# Sensor.net
KiCad netlist of a schematic drawn in Altium Designer
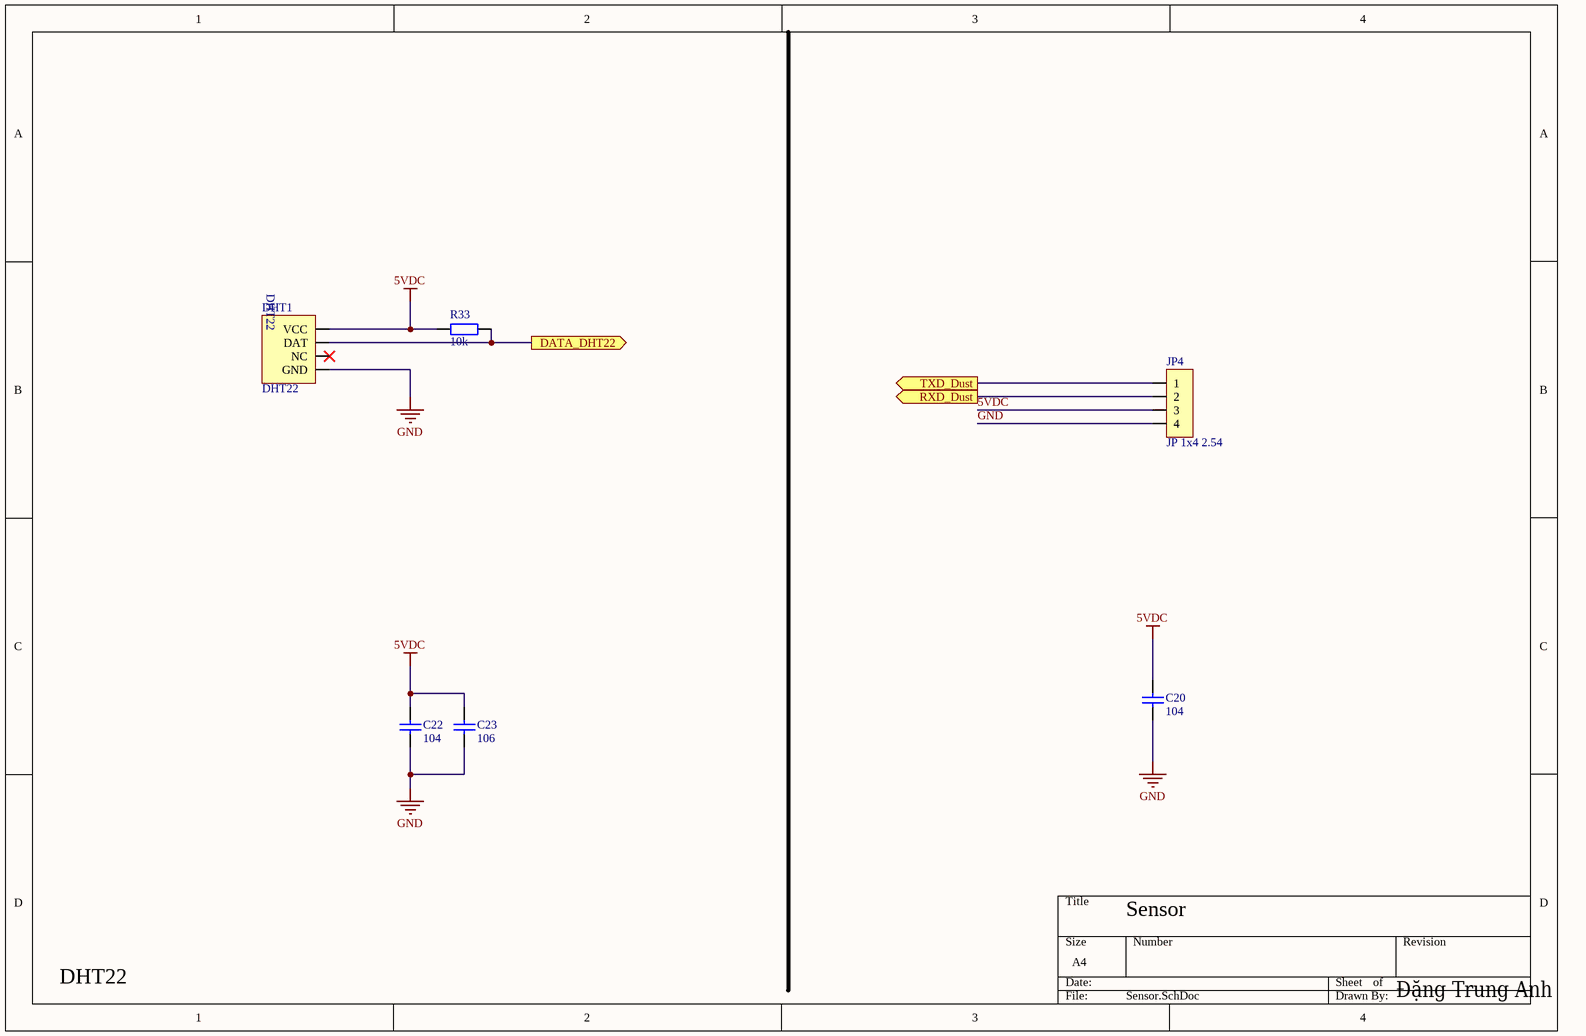
[diagram p0: Sensor.SchDoc]

(export (version "E")
  (design (tool "Eeschema 10.0.6"))
  (components
    (comp (ref "C20")
      (value "104")
      (footprint "tu 0603")
      (description "Dán")
      (libsource (lib "Altium_Lib_by_KhueNguyenCreator") (part "Tu 0603 104 50V 10%"))
    )
    (comp (ref "C22")
      (value "104")
      (footprint "tu 0603")
      (description "Dán")
      (libsource (lib "Altium_Lib_by_KhueNguyenCreator") (part "Tu 0603 104 50V 10%"))
    )
    (comp (ref "C23")
      (value "106")
      (footprint "tu 0603")
      (description "Dán")
      (libsource (lib "THU VIEN SCH") (part "Tu 0603 106 16V 20%"))
    )
    (comp (ref "DHT1")
      (value "DHT22")
      (footprint "DHT22")
      (fields
        (field (name "MANUFACTURER") "Würth Elektronik eiSos GmbH")
        (field (name "PARTNO") "613004143121")
        (field (name "CREATED BY") "Karrer Zheng")
      )
      (libsource (lib "TechMT.VN_Lib_Project v2") (part "DHT22"))
    )
    (comp (ref "JP4")
      (value "JP 1x4 2.54")
      (footprint "JP 1x4 DC")
      (description "Cắm")
      (libsource (lib "Altium_Lib_by_KhueNguyenCreator") (part "JP 1x4 2.54 Duc Cong"))
    )
    (comp (ref "R33")
      (value "10k")
      (footprint "tro smd 0603")
      (description "Dán")
      (libsource (lib "THU VIEN SCH") (part "Tro 0603 1% 10k"))
    )
  )
  (nets
    (net (code "1") (name "/DATA_DHT22") (class "Default")
      (node (ref "DHT1") (pin "2") (pinfunction "DAT_2") (pintype "passive"))
      (node (ref "R33") (pin "1") (pinfunction "1_1") (pintype "passive"))
    )
    (net (code "2") (name "/RXD_Dust") (class "Default")
      (node (ref "JP4") (pin "2") (pinfunction "2_2") (pintype "passive"))
    )
    (net (code "3") (name "/TXD_Dust") (class "Default")
      (node (ref "JP4") (pin "1") (pinfunction "1_1") (pintype "passive"))
    )
    (net (code "4") (name "5VDC") (class "Default")
      (node (ref "C20") (pin "1") (pinfunction "1_1") (pintype "passive"))
      (node (ref "C22") (pin "1") (pinfunction "1_1") (pintype "passive"))
      (node (ref "C23") (pin "1") (pinfunction "1_1") (pintype "passive"))
      (node (ref "DHT1") (pin "1") (pinfunction "VCC_1") (pintype "passive"))
      (node (ref "JP4") (pin "3") (pinfunction "3_3") (pintype "passive"))
      (node (ref "R33") (pin "2") (pinfunction "2_2") (pintype "passive"))
    )
    (net (code "5") (name "GND") (class "Default")
      (node (ref "C20") (pin "2") (pinfunction "2_2") (pintype "passive"))
      (node (ref "C22") (pin "2") (pinfunction "2_2") (pintype "passive"))
      (node (ref "C23") (pin "2") (pinfunction "2_2") (pintype "passive"))
      (node (ref "DHT1") (pin "4") (pinfunction "GND_4") (pintype "passive"))
      (node (ref "JP4") (pin "4") (pinfunction "4_4") (pintype "passive"))
    )
    (net (code "6") (name "unconnected-(DHT1-NC-Pad3)") (class "Default")
      (node (ref "DHT1") (pin "3") (pinfunction "NC_3") (pintype "passive+no_connect"))
    )
  )
)
